# IRPKrancowki.net
KiCad netlist of a schematic drawn in Altium Designer
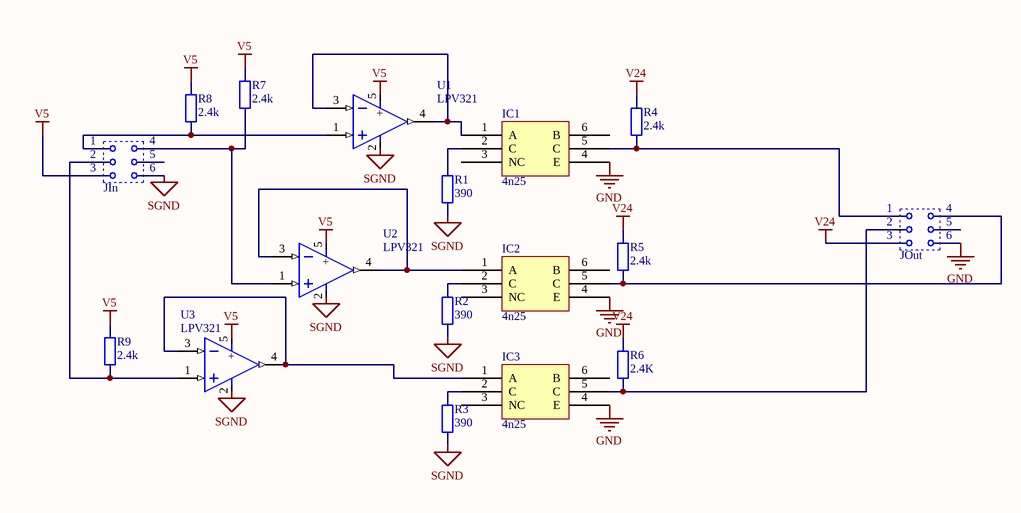
[diagram p0: IRPKrancowki.SchDoc]

(export (version "E")
  (design (tool "Eeschema 10.0.6"))
  (components
    (comp (ref "IC1") (value "4n25") (footprint "DIP6") (libsource (lib "IC-Opto") (part "4n25")))
    (comp (ref "IC2") (value "4n25") (footprint "DIP6") (libsource (lib "IC-Opto") (part "4n25")))
    (comp (ref "IC3") (value "4n25") (footprint "DIP6") (libsource (lib "IC-Opto") (part "4n25")))
    (comp (ref "JIn")
      (value "Molex Microfit")
      (footprint "MicroFit:MICROFIT 3x2 Right Angle")
      (libsource (lib "Connectors") (part "Microfit 3x2"))
    )
    (comp (ref "JOut")
      (value "Molex Microfit")
      (footprint "MicroFit:MICROFIT 3x2 Right Angle")
      (libsource (lib "Connectors") (part "Microfit 3x2"))
    )
    (comp (ref "R1")
      (value "390")
      (footprint "Other-Discrete:1206_R")
      (description "Resistor")
      (libsource (lib "Disc-Other") (part "R"))
    )
    (comp (ref "R2")
      (value "390")
      (footprint "Other-Discrete:1206_R")
      (description "Resistor")
      (libsource (lib "Disc-Other") (part "R"))
    )
    (comp (ref "R3")
      (value "390")
      (footprint "Other-Discrete:1206_R")
      (description "Resistor")
      (libsource (lib "Disc-Other") (part "R"))
    )
    (comp (ref "R4")
      (value "2.4k")
      (footprint "Other-Discrete:1206_R")
      (description "Resistor")
      (libsource (lib "Disc-Other") (part "R"))
    )
    (comp (ref "R5")
      (value "2.4k")
      (footprint "Other-Discrete:1206_R")
      (description "Resistor")
      (libsource (lib "Disc-Other") (part "R"))
    )
    (comp (ref "R6")
      (value "2.4K")
      (footprint "Other-Discrete:1206_R")
      (description "Resistor")
      (libsource (lib "Disc-Other") (part "R"))
    )
    (comp (ref "R7")
      (value "2.4k")
      (footprint "Other-Discrete:1206_R")
      (description "Resistor")
      (libsource (lib "Disc-Other") (part "R"))
    )
    (comp (ref "R8")
      (value "2.4k")
      (footprint "Other-Discrete:1206_R")
      (description "Resistor")
      (libsource (lib "Disc-Other") (part "R"))
    )
    (comp (ref "R9")
      (value "2.4k")
      (footprint "Other-Discrete:1206_R")
      (description "Resistor")
      (libsource (lib "Disc-Other") (part "R"))
    )
    (comp (ref "U1") (value "LPV321") (footprint "5SOT-23") (libsource (lib "IC-OpAmp") (part "LPV321")))
    (comp (ref "U2") (value "LPV321") (footprint "5SOT-23") (libsource (lib "IC-OpAmp") (part "LPV321")))
    (comp (ref "U3") (value "LPV321") (footprint "5SOT-23") (libsource (lib "IC-OpAmp") (part "LPV321")))
  )
  (nets
    (net (code "1") (name "GND") (class "Default")
      (node (ref "IC1") (pin "4") (pinfunction "E_4") (pintype "passive"))
      (node (ref "IC2") (pin "4") (pinfunction "E_4") (pintype "passive"))
      (node (ref "IC3") (pin "4") (pinfunction "E_4") (pintype "passive"))
      (node (ref "JOut") (pin "6") (pintype "passive"))
    )
    (net (code "2") (name "Net-(IC1-A)") (class "Default")
      (node (ref "IC1") (pin "1") (pinfunction "A_1") (pintype "passive"))
      (node (ref "U1") (pin "3") (pinfunction "IN-_3") (pintype "input"))
      (node (ref "U1") (pin "4") (pinfunction "OUT_4") (pintype "output"))
    )
    (net (code "3") (name "Net-(IC1-C-Pad2)") (class "Default")
      (node (ref "IC1") (pin "2") (pinfunction "C_2") (pintype "passive"))
      (node (ref "R1") (pin "2") (pinfunction "2_2") (pintype "passive"))
    )
    (net (code "4") (name "Net-(IC1-C-Pad5)") (class "Default")
      (node (ref "IC1") (pin "5") (pinfunction "C_5") (pintype "passive"))
      (node (ref "JOut") (pin "1") (pintype "passive"))
      (node (ref "R4") (pin "1") (pinfunction "1_1") (pintype "passive"))
    )
    (net (code "5") (name "Net-(IC2-A)") (class "Default")
      (node (ref "IC2") (pin "1") (pinfunction "A_1") (pintype "passive"))
      (node (ref "U2") (pin "3") (pinfunction "IN-_3") (pintype "input"))
      (node (ref "U2") (pin "4") (pinfunction "OUT_4") (pintype "output"))
    )
    (net (code "6") (name "Net-(IC2-C-Pad2)") (class "Default")
      (node (ref "IC2") (pin "2") (pinfunction "C_2") (pintype "passive"))
      (node (ref "R2") (pin "2") (pinfunction "2_2") (pintype "passive"))
    )
    (net (code "7") (name "Net-(IC2-C-Pad5)") (class "Default")
      (node (ref "IC2") (pin "5") (pinfunction "C_5") (pintype "passive"))
      (node (ref "JOut") (pin "4") (pintype "passive"))
      (node (ref "R5") (pin "1") (pinfunction "1_1") (pintype "passive"))
    )
    (net (code "8") (name "Net-(IC3-A)") (class "Default")
      (node (ref "IC3") (pin "1") (pinfunction "A_1") (pintype "passive"))
      (node (ref "U3") (pin "3") (pinfunction "IN-_3") (pintype "input"))
      (node (ref "U3") (pin "4") (pinfunction "OUT_4") (pintype "output"))
    )
    (net (code "9") (name "Net-(IC3-C-Pad2)") (class "Default")
      (node (ref "IC3") (pin "2") (pinfunction "C_2") (pintype "passive"))
      (node (ref "R3") (pin "2") (pinfunction "2_2") (pintype "passive"))
    )
    (net (code "10") (name "Net-(IC3-C-Pad5)") (class "Default")
      (node (ref "IC3") (pin "5") (pinfunction "C_5") (pintype "passive"))
      (node (ref "JOut") (pin "2") (pintype "passive"))
      (node (ref "R6") (pin "1") (pinfunction "1_1") (pintype "passive"))
    )
    (net (code "11") (name "Net-(U1-IN+)") (class "Default")
      (node (ref "JIn") (pin "1") (pintype "passive"))
      (node (ref "R8") (pin "1") (pinfunction "1_1") (pintype "passive"))
      (node (ref "U1") (pin "1") (pinfunction "IN+_1") (pintype "input"))
    )
    (net (code "12") (name "Net-(U2-IN+)") (class "Default")
      (node (ref "JIn") (pin "4") (pintype "passive"))
      (node (ref "R7") (pin "1") (pinfunction "1_1") (pintype "passive"))
      (node (ref "U2") (pin "1") (pinfunction "IN+_1") (pintype "input"))
    )
    (net (code "13") (name "Net-(U3-IN+)") (class "Default")
      (node (ref "JIn") (pin "2") (pintype "passive"))
      (node (ref "R9") (pin "1") (pinfunction "1_1") (pintype "passive"))
      (node (ref "U3") (pin "1") (pinfunction "IN+_1") (pintype "input"))
    )
    (net (code "14") (name "SGND") (class "Default")
      (node (ref "JIn") (pin "6") (pintype "passive"))
      (node (ref "R1") (pin "1") (pinfunction "1_1") (pintype "passive"))
      (node (ref "R2") (pin "1") (pinfunction "1_1") (pintype "passive"))
      (node (ref "R3") (pin "1") (pinfunction "1_1") (pintype "passive"))
      (node (ref "U1") (pin "2") (pinfunction "-_2") (pintype "power_in"))
      (node (ref "U2") (pin "2") (pinfunction "-_2") (pintype "power_in"))
      (node (ref "U3") (pin "2") (pinfunction "-_2") (pintype "power_in"))
    )
    (net (code "15") (name "V5") (class "Default")
      (node (ref "JIn") (pin "3") (pintype "passive"))
      (node (ref "R7") (pin "2") (pinfunction "2_2") (pintype "passive"))
      (node (ref "R8") (pin "2") (pinfunction "2_2") (pintype "passive"))
      (node (ref "R9") (pin "2") (pinfunction "2_2") (pintype "passive"))
      (node (ref "U1") (pin "5") (pinfunction "+_5") (pintype "power_in"))
      (node (ref "U2") (pin "5") (pinfunction "+_5") (pintype "power_in"))
      (node (ref "U3") (pin "5") (pinfunction "+_5") (pintype "power_in"))
    )
    (net (code "16") (name "V24") (class "Default")
      (node (ref "JOut") (pin "3") (pintype "passive"))
      (node (ref "R4") (pin "2") (pinfunction "2_2") (pintype "passive"))
      (node (ref "R5") (pin "2") (pinfunction "2_2") (pintype "passive"))
      (node (ref "R6") (pin "2") (pinfunction "2_2") (pintype "passive"))
    )
    (net (code "17") (name "unconnected-(IC1-B-Pad6)") (class "Default")
      (node (ref "IC1") (pin "6") (pinfunction "B_6") (pintype "passive"))
    )
    (net (code "18") (name "unconnected-(IC1-NC-Pad3)") (class "Default")
      (node (ref "IC1") (pin "3") (pinfunction "NC_3") (pintype "passive"))
    )
    (net (code "19") (name "unconnected-(IC2-B-Pad6)") (class "Default")
      (node (ref "IC2") (pin "6") (pinfunction "B_6") (pintype "passive"))
    )
    (net (code "20") (name "unconnected-(IC2-NC-Pad3)") (class "Default")
      (node (ref "IC2") (pin "3") (pinfunction "NC_3") (pintype "passive"))
    )
    (net (code "21") (name "unconnected-(IC3-B-Pad6)") (class "Default")
      (node (ref "IC3") (pin "6") (pinfunction "B_6") (pintype "passive"))
    )
    (net (code "22") (name "unconnected-(IC3-NC-Pad3)") (class "Default")
      (node (ref "IC3") (pin "3") (pinfunction "NC_3") (pintype "passive"))
    )
    (net (code "23") (name "unconnected-(JIn-Pad5)") (class "Default")
      (node (ref "JIn") (pin "5") (pintype "passive"))
    )
    (net (code "24") (name "unconnected-(JOut-Pad5)") (class "Default")
      (node (ref "JOut") (pin "5") (pintype "passive"))
    )
  )
)
